# shield-st7735_1_8-spi-UNO-r4.net
KiCad netlist of a schematic drawn in EAGLE
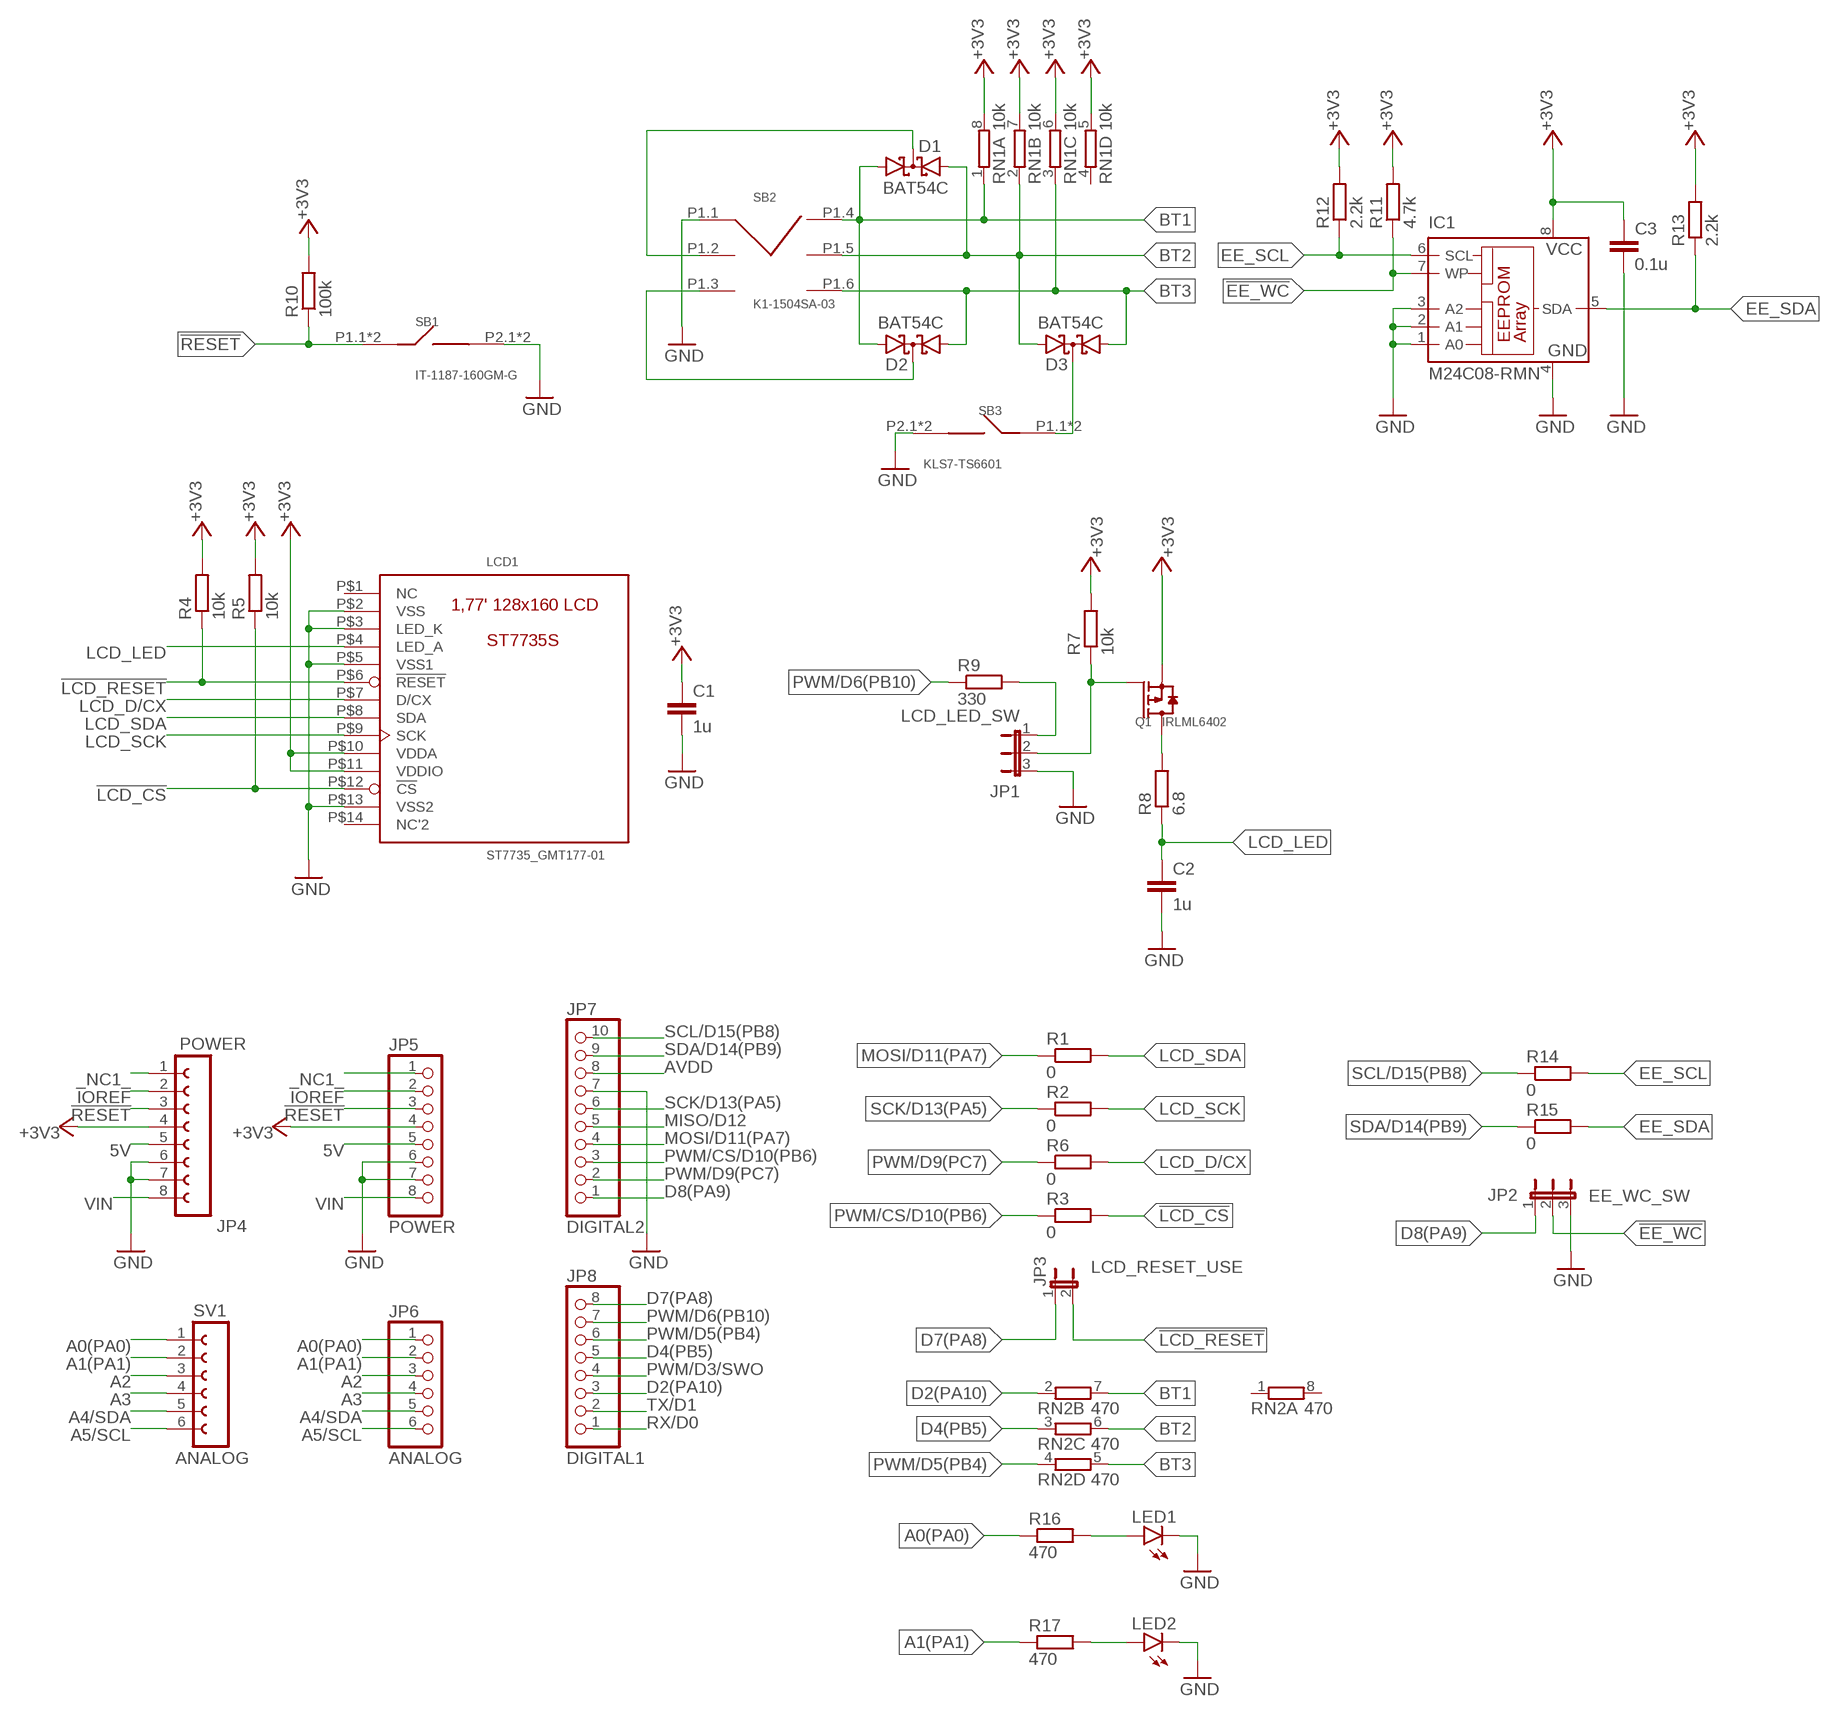
[diagram p0: schematic, sheet 1]

(export (version "E")
  (design (tool "Eeschema 10.0.6"))
  (components
    (comp (ref "C1")
      (value "1u")
      (footprint "eagle-import:C1206")
      (libsource (lib "eagle-import") (part "C-EUC1206"))
    )
    (comp (ref "C2")
      (value "1u")
      (footprint "eagle-import:C1206")
      (libsource (lib "eagle-import") (part "C-EUC1206"))
    )
    (comp (ref "C3")
      (value "0.1u")
      (footprint "eagle-import:C1206")
      (libsource (lib "eagle-import") (part "C-EUC1206"))
    )
    (comp (ref "D1")
      (value "BAT54C")
      (footprint "eagle-import:SOT23")
      (libsource (lib "eagle-import") (part "BAT54C"))
    )
    (comp (ref "D2")
      (value "BAT54C")
      (footprint "eagle-import:SOT23")
      (libsource (lib "eagle-import") (part "BAT54C"))
    )
    (comp (ref "D3")
      (value "BAT54C")
      (footprint "eagle-import:SOT23")
      (libsource (lib "eagle-import") (part "BAT54C"))
    )
    (comp (ref "IC1")
      (value "M24C08-RMN")
      (footprint "eagle-import:SO-08")
      (fields (field (name "MPN") "24LC08B/SN"))
      (libsource (lib "eagle-import") (part "24SNLC08B"))
    )
    (comp (ref "JP1")
      (value "LCD_LED_SW")
      (footprint "eagle-import:JP2")
      (libsource (lib "eagle-import") (part "JP2E"))
    )
    (comp (ref "JP2")
      (value "EE_WC_SW")
      (footprint "eagle-import:JP2")
      (libsource (lib "eagle-import") (part "JP2E"))
    )
    (comp (ref "JP3")
      (value "LCD_RESET_USE")
      (footprint "eagle-import:JP1")
      (libsource (lib "eagle-import") (part "JP1E"))
    )
    (comp (ref "JP4")
      (value "POWER")
      (footprint "eagle-import:FE08")
      (libsource (lib "eagle-import") (part "FE08-1"))
    )
    (comp (ref "JP5")
      (value "POWER")
      (footprint "eagle-import:1X08")
      (libsource (lib "eagle-import") (part "PINHD-1X8"))
    )
    (comp (ref "JP6")
      (value "ANALOG")
      (footprint "eagle-import:1X06")
      (libsource (lib "eagle-import") (part "PINHD-1X6"))
    )
    (comp (ref "JP7")
      (value "DIGITAL2")
      (footprint "eagle-import:1X10")
      (libsource (lib "eagle-import") (part "PINHD-1X10"))
    )
    (comp (ref "JP8")
      (value "DIGITAL1")
      (footprint "eagle-import:1X08")
      (libsource (lib "eagle-import") (part "PINHD-1X8"))
    )
    (comp (ref "LCD1")
      (value "ST7735_GMT177-01")
      (footprint "eagle-import:GMT177-01")
      (libsource (lib "eagle-import") (part "ST7735_GMT177-01"))
    )
    (comp (ref "LED1")
      (value "LEDCHIP-LED0805")
      (footprint "eagle-import:CHIP-LED0805")
      (libsource (lib "eagle-import") (part "LEDCHIP-LED0805"))
    )
    (comp (ref "LED2")
      (value "LEDCHIP-LED0805")
      (footprint "eagle-import:CHIP-LED0805")
      (libsource (lib "eagle-import") (part "LEDCHIP-LED0805"))
    )
    (comp (ref "Q1")
      (value "IRLML6402")
      (footprint "eagle-import:SOT23")
      (libsource (lib "eagle-import") (part "IRLML6402"))
    )
    (comp (ref "R1")
      (value "0")
      (footprint "eagle-import:R1206")
      (libsource (lib "eagle-import") (part "R-EU_R1206"))
    )
    (comp (ref "R2")
      (value "0")
      (footprint "eagle-import:R1206")
      (libsource (lib "eagle-import") (part "R-EU_R1206"))
    )
    (comp (ref "R3")
      (value "0")
      (footprint "eagle-import:R1206")
      (libsource (lib "eagle-import") (part "R-EU_R1206"))
    )
    (comp (ref "R4")
      (value "10k")
      (footprint "eagle-import:R1206")
      (libsource (lib "eagle-import") (part "R-EU_R1206"))
    )
    (comp (ref "R5")
      (value "10k")
      (footprint "eagle-import:R1206")
      (libsource (lib "eagle-import") (part "R-EU_R1206"))
    )
    (comp (ref "R6")
      (value "0")
      (footprint "eagle-import:R1206")
      (libsource (lib "eagle-import") (part "R-EU_R1206"))
    )
    (comp (ref "R7")
      (value "10k")
      (footprint "eagle-import:R1206")
      (libsource (lib "eagle-import") (part "R-EU_R1206"))
    )
    (comp (ref "R8")
      (value "6.8")
      (footprint "eagle-import:R1206")
      (libsource (lib "eagle-import") (part "R-EU_R1206"))
    )
    (comp (ref "R9")
      (value "330")
      (footprint "eagle-import:R1206")
      (libsource (lib "eagle-import") (part "R-EU_R1206"))
    )
    (comp (ref "R10")
      (value "100k")
      (footprint "eagle-import:R1206")
      (libsource (lib "eagle-import") (part "R-EU_R1206"))
    )
    (comp (ref "R11")
      (value "4.7k")
      (footprint "eagle-import:R1206")
      (libsource (lib "eagle-import") (part "R-EU_R1206"))
    )
    (comp (ref "R12")
      (value "2.2k")
      (footprint "eagle-import:R1206")
      (libsource (lib "eagle-import") (part "R-EU_R1206"))
    )
    (comp (ref "R13")
      (value "2.2k")
      (footprint "eagle-import:R1206")
      (libsource (lib "eagle-import") (part "R-EU_R1206"))
    )
    (comp (ref "R14")
      (value "0")
      (footprint "eagle-import:R1206")
      (libsource (lib "eagle-import") (part "R-EU_R1206"))
    )
    (comp (ref "R15")
      (value "0")
      (footprint "eagle-import:R1206")
      (libsource (lib "eagle-import") (part "R-EU_R1206"))
    )
    (comp (ref "R16")
      (value "470")
      (footprint "eagle-import:R1206")
      (libsource (lib "eagle-import") (part "R-EU_R1206"))
    )
    (comp (ref "R17")
      (value "470")
      (footprint "eagle-import:R1206")
      (libsource (lib "eagle-import") (part "R-EU_R1206"))
    )
    (comp (ref "RN1")
      (value "10k")
      (footprint "eagle-import:EXB38V")
      (libsource (lib "eagle-import") (part "4R-NEXB38V"))
    )
    (comp (ref "RN2")
      (value "470")
      (footprint "eagle-import:EXB38V")
      (libsource (lib "eagle-import") (part "4R-NEXB38V"))
    )
    (comp (ref "SB1")
      (value "IT-1187-160GM-G")
      (footprint "eagle-import:IT-1187-160GM-G")
      (libsource (lib "eagle-import") (part "IT-1187-160GM-G"))
    )
    (comp (ref "SB2")
      (value "K1-1504SA-03")
      (footprint "eagle-import:K1-1504SA-3")
      (libsource (lib "eagle-import") (part "K1-1504SA-03"))
    )
    (comp (ref "SB3")
      (value "KLS7-TS6601")
      (footprint "eagle-import:KLS7-TS6601")
      (libsource (lib "eagle-import") (part "KLS7-TS6601"))
    )
    (comp (ref "SV1")
      (value "ANALOG")
      (footprint "eagle-import:FE06")
      (libsource (lib "eagle-import") (part "FE06-1"))
    )
  )
  (nets
    (net (code "1") (name "+3V3") (class "Default")
      (node (ref "C1") (pin "1") (pinfunction "1_1") (pintype "passive"))
      (node (ref "C3") (pin "1") (pinfunction "1_1") (pintype "passive"))
      (node (ref "IC1") (pin "8") (pinfunction "VCC_8") (pintype "power_in"))
      (node (ref "JP4") (pin "4") (pinfunction "4_4") (pintype "passive"))
      (node (ref "JP5") (pin "4") (pinfunction "4_4") (pintype "passive"))
      (node (ref "LCD1") (pin "P$10") (pinfunction "VDDA_P$10") (pintype "power_in"))
      (node (ref "LCD1") (pin "P$11") (pinfunction "VDDIO_P$11") (pintype "power_in"))
      (node (ref "Q1") (pin "2") (pinfunction "S_2") (pintype "passive"))
      (node (ref "R10") (pin "2") (pinfunction "2_2") (pintype "passive"))
      (node (ref "R11") (pin "2") (pinfunction "2_2") (pintype "passive"))
      (node (ref "R12") (pin "2") (pinfunction "2_2") (pintype "passive"))
      (node (ref "R13") (pin "2") (pinfunction "2_2") (pintype "passive"))
      (node (ref "R4") (pin "2") (pinfunction "2_2") (pintype "passive"))
      (node (ref "R5") (pin "2") (pinfunction "2_2") (pintype "passive"))
      (node (ref "R7") (pin "2") (pinfunction "2_2") (pintype "passive"))
      (node (ref "RN1") (pin "5") (pinfunction "2_5") (pintype "passive"))
      (node (ref "RN1") (pin "6") (pinfunction "2_6") (pintype "passive"))
      (node (ref "RN1") (pin "7") (pinfunction "2_7") (pintype "passive"))
      (node (ref "RN1") (pin "8") (pinfunction "2_8") (pintype "passive"))
    )
    (net (code "2") (name "/5V") (class "Default")
      (node (ref "JP4") (pin "5") (pinfunction "5_5") (pintype "passive"))
      (node (ref "JP5") (pin "5") (pinfunction "5_5") (pintype "passive"))
    )
    (net (code "3") (name "/A2") (class "Default")
      (node (ref "JP6") (pin "3") (pinfunction "3_3") (pintype "passive"))
      (node (ref "SV1") (pin "3") (pinfunction "3_3") (pintype "passive"))
    )
    (net (code "4") (name "/A3") (class "Default")
      (node (ref "JP6") (pin "4") (pinfunction "4_4") (pintype "passive"))
      (node (ref "SV1") (pin "4") (pinfunction "4_4") (pintype "passive"))
    )
    (net (code "5") (name "/A4{slash}SDA") (class "Default")
      (node (ref "JP6") (pin "5") (pinfunction "5_5") (pintype "passive"))
      (node (ref "SV1") (pin "5") (pinfunction "5_5") (pintype "passive"))
    )
    (net (code "6") (name "/A5{slash}SCL") (class "Default")
      (node (ref "JP6") (pin "6") (pinfunction "6_6") (pintype "passive"))
      (node (ref "SV1") (pin "6") (pinfunction "6_6") (pintype "passive"))
    )
    (net (code "7") (name "/AVDD") (class "Default")
      (node (ref "JP7") (pin "8") (pinfunction "8_8") (pintype "passive"))
    )
    (net (code "8") (name "/IOREF") (class "Default")
      (node (ref "JP4") (pin "2") (pinfunction "2_2") (pintype "passive"))
      (node (ref "JP5") (pin "2") (pinfunction "2_2") (pintype "passive"))
    )
    (net (code "9") (name "/MISO{slash}D12") (class "Default")
      (node (ref "JP7") (pin "5") (pinfunction "5_5") (pintype "passive"))
    )
    (net (code "10") (name "/PWM{slash}D3{slash}SWO") (class "Default")
      (node (ref "JP8") (pin "4") (pinfunction "4_4") (pintype "passive"))
    )
    (net (code "11") (name "/RX{slash}D0") (class "Default")
      (node (ref "JP8") (pin "1") (pinfunction "1_1") (pintype "passive"))
    )
    (net (code "12") (name "/TX{slash}D1") (class "Default")
      (node (ref "JP8") (pin "2") (pinfunction "2_2") (pintype "passive"))
    )
    (net (code "13") (name "/VIN") (class "Default")
      (node (ref "JP4") (pin "8") (pinfunction "8_8") (pintype "passive"))
      (node (ref "JP5") (pin "8") (pinfunction "8_8") (pintype "passive"))
    )
    (net (code "14") (name "/_NC1_") (class "Default")
      (node (ref "JP4") (pin "1") (pinfunction "1_1") (pintype "passive"))
      (node (ref "JP5") (pin "1") (pinfunction "1_1") (pintype "passive"))
    )
    (net (code "15") (name "/~{EE_WC}") (class "Default")
      (node (ref "IC1") (pin "7") (pinfunction "WP_7") (pintype "input"))
      (node (ref "JP2") (pin "2") (pinfunction "2_2") (pintype "passive"))
      (node (ref "R11") (pin "1") (pinfunction "1_1") (pintype "passive"))
    )
    (net (code "16") (name "/~{LCD_CS}") (class "Default")
      (node (ref "LCD1") (pin "P$12") (pinfunction "~{CS}_P$12") (pintype "input"))
      (node (ref "R3") (pin "2") (pinfunction "2_2") (pintype "passive"))
      (node (ref "R5") (pin "1") (pinfunction "1_1") (pintype "passive"))
    )
    (net (code "17") (name "/~{LCD_RESET}") (class "Default")
      (node (ref "JP3") (pin "2") (pinfunction "2_2") (pintype "passive"))
      (node (ref "LCD1") (pin "P$6") (pinfunction "~{RESET}_P$6") (pintype "input"))
      (node (ref "R4") (pin "1") (pinfunction "1_1") (pintype "passive"))
    )
    (net (code "18") (name "/~{RESET}") (class "Default")
      (node (ref "JP4") (pin "3") (pinfunction "3_3") (pintype "passive"))
      (node (ref "JP5") (pin "3") (pinfunction "3_3") (pintype "passive"))
      (node (ref "R10") (pin "1") (pinfunction "1_1") (pintype "passive"))
      (node (ref "SB1") (pin "P1.1") (pinfunction "P1_P1.1") (pintype "bidirectional"))
      (node (ref "SB1") (pin "P1.2") (pinfunction "P1_P1.2") (pintype "bidirectional"))
    )
    (net (code "19") (name "A0(PA0)") (class "Default")
      (node (ref "JP6") (pin "1") (pinfunction "1_1") (pintype "passive"))
      (node (ref "R16") (pin "1") (pinfunction "1_1") (pintype "passive"))
      (node (ref "SV1") (pin "1") (pinfunction "1_1") (pintype "passive"))
    )
    (net (code "20") (name "A1(PA1)") (class "Default")
      (node (ref "JP6") (pin "2") (pinfunction "2_2") (pintype "passive"))
      (node (ref "R17") (pin "1") (pinfunction "1_1") (pintype "passive"))
      (node (ref "SV1") (pin "2") (pinfunction "2_2") (pintype "passive"))
    )
    (net (code "21") (name "BT1") (class "Default")
      (node (ref "D1") (pin "1") (pinfunction "A1_1") (pintype "passive"))
      (node (ref "D2") (pin "2") (pinfunction "A2_2") (pintype "passive"))
      (node (ref "RN1") (pin "1") (pinfunction "1_1") (pintype "passive"))
      (node (ref "RN2") (pin "7") (pinfunction "2_7") (pintype "passive"))
      (node (ref "SB2") (pin "P1.4") (pinfunction "P4_P1.4") (pintype "bidirectional"))
    )
    (net (code "22") (name "BT2") (class "Default")
      (node (ref "D1") (pin "2") (pinfunction "A2_2") (pintype "passive"))
      (node (ref "D3") (pin "2") (pinfunction "A2_2") (pintype "passive"))
      (node (ref "RN1") (pin "2") (pinfunction "1_2") (pintype "passive"))
      (node (ref "RN2") (pin "6") (pinfunction "2_6") (pintype "passive"))
      (node (ref "SB2") (pin "P1.5") (pinfunction "P5_P1.5") (pintype "bidirectional"))
    )
    (net (code "23") (name "BT3") (class "Default")
      (node (ref "D2") (pin "1") (pinfunction "A1_1") (pintype "passive"))
      (node (ref "D3") (pin "1") (pinfunction "A1_1") (pintype "passive"))
      (node (ref "RN1") (pin "3") (pinfunction "1_3") (pintype "passive"))
      (node (ref "RN2") (pin "5") (pinfunction "2_5") (pintype "passive"))
      (node (ref "SB2") (pin "P1.6") (pinfunction "P6_P1.6") (pintype "bidirectional"))
    )
    (net (code "24") (name "D2(PA10)") (class "Default")
      (node (ref "JP8") (pin "3") (pinfunction "3_3") (pintype "passive"))
      (node (ref "RN2") (pin "2") (pinfunction "1_2") (pintype "passive"))
    )
    (net (code "25") (name "D4(PB5)") (class "Default")
      (node (ref "JP8") (pin "5") (pinfunction "5_5") (pintype "passive"))
      (node (ref "RN2") (pin "3") (pinfunction "1_3") (pintype "passive"))
    )
    (net (code "26") (name "D7(PA8)") (class "Default")
      (node (ref "JP3") (pin "1") (pinfunction "1_1") (pintype "passive"))
      (node (ref "JP8") (pin "8") (pinfunction "8_8") (pintype "passive"))
    )
    (net (code "27") (name "D8(PA9)") (class "Default")
      (node (ref "JP2") (pin "1") (pinfunction "1_1") (pintype "passive"))
      (node (ref "JP7") (pin "1") (pinfunction "1_1") (pintype "passive"))
    )
    (net (code "28") (name "EE_SCL") (class "Default")
      (node (ref "IC1") (pin "6") (pinfunction "SCL_6") (pintype "input"))
      (node (ref "R12") (pin "1") (pinfunction "1_1") (pintype "passive"))
      (node (ref "R14") (pin "2") (pinfunction "2_2") (pintype "passive"))
    )
    (net (code "29") (name "EE_SDA") (class "Default")
      (node (ref "IC1") (pin "5") (pinfunction "SDA_5") (pintype "bidirectional"))
      (node (ref "R13") (pin "1") (pinfunction "1_1") (pintype "passive"))
      (node (ref "R15") (pin "2") (pinfunction "2_2") (pintype "passive"))
    )
    (net (code "30") (name "GND") (class "Default")
      (node (ref "C1") (pin "2") (pinfunction "2_2") (pintype "passive"))
      (node (ref "C2") (pin "2") (pinfunction "2_2") (pintype "passive"))
      (node (ref "C3") (pin "2") (pinfunction "2_2") (pintype "passive"))
      (node (ref "IC1") (pin "1") (pinfunction "A0_1") (pintype "input"))
      (node (ref "IC1") (pin "2") (pinfunction "A1_2") (pintype "input"))
      (node (ref "IC1") (pin "3") (pinfunction "A2_3") (pintype "input"))
      (node (ref "IC1") (pin "4") (pinfunction "GND_4") (pintype "power_in"))
      (node (ref "JP1") (pin "3") (pinfunction "3_3") (pintype "passive"))
      (node (ref "JP2") (pin "3") (pinfunction "3_3") (pintype "passive"))
      (node (ref "JP4") (pin "6") (pinfunction "6_6") (pintype "passive"))
      (node (ref "JP4") (pin "7") (pinfunction "7_7") (pintype "passive"))
      (node (ref "JP5") (pin "6") (pinfunction "6_6") (pintype "passive"))
      (node (ref "JP5") (pin "7") (pinfunction "7_7") (pintype "passive"))
      (node (ref "JP7") (pin "7") (pinfunction "7_7") (pintype "passive"))
      (node (ref "LCD1") (pin "P$13") (pinfunction "VSS2_P$13") (pintype "power_in"))
      (node (ref "LCD1") (pin "P$2") (pinfunction "VSS_P$2") (pintype "power_in"))
      (node (ref "LCD1") (pin "P$3") (pinfunction "LED_K_P$3") (pintype "bidirectional"))
      (node (ref "LCD1") (pin "P$5") (pinfunction "VSS1_P$5") (pintype "power_in"))
      (node (ref "LED1") (pin "C") (pinfunction "C_C") (pintype "passive"))
      (node (ref "LED2") (pin "C") (pinfunction "C_C") (pintype "passive"))
      (node (ref "SB1") (pin "P2.1") (pinfunction "P2_P2.1") (pintype "bidirectional"))
      (node (ref "SB1") (pin "P2.2") (pinfunction "P2_P2.2") (pintype "bidirectional"))
      (node (ref "SB2") (pin "P1.1") (pinfunction "P1_P1.1") (pintype "bidirectional"))
      (node (ref "SB3") (pin "P2.1") (pinfunction "P2_P2.1") (pintype "bidirectional"))
      (node (ref "SB3") (pin "P2.2") (pinfunction "P2_P2.2") (pintype "bidirectional"))
    )
    (net (code "31") (name "LCD_D{slash}CX") (class "Default")
      (node (ref "LCD1") (pin "P$7") (pinfunction "D/CX_P$7") (pintype "input"))
      (node (ref "R6") (pin "2") (pinfunction "2_2") (pintype "passive"))
    )
    (net (code "32") (name "LCD_LED") (class "Default")
      (node (ref "C2") (pin "1") (pinfunction "1_1") (pintype "passive"))
      (node (ref "LCD1") (pin "P$4") (pinfunction "LED_A_P$4") (pintype "input"))
      (node (ref "R8") (pin "1") (pinfunction "1_1") (pintype "passive"))
    )
    (net (code "33") (name "LCD_SCK") (class "Default")
      (node (ref "LCD1") (pin "P$9") (pinfunction "SCK_P$9") (pintype "bidirectional"))
      (node (ref "R2") (pin "2") (pinfunction "2_2") (pintype "passive"))
    )
    (net (code "34") (name "LCD_SDA") (class "Default")
      (node (ref "LCD1") (pin "P$8") (pinfunction "SDA_P$8") (pintype "bidirectional"))
      (node (ref "R1") (pin "2") (pinfunction "2_2") (pintype "passive"))
    )
    (net (code "35") (name "MOSI{slash}D11(PA7)") (class "Default")
      (node (ref "JP7") (pin "4") (pinfunction "4_4") (pintype "passive"))
      (node (ref "R1") (pin "1") (pinfunction "1_1") (pintype "passive"))
    )
    (net (code "36") (name "Net-(D1-CC)") (class "Default")
      (node (ref "D1") (pin "3") (pinfunction "CC_3") (pintype "passive"))
      (node (ref "SB2") (pin "P1.2") (pinfunction "P2_P1.2") (pintype "bidirectional"))
    )
    (net (code "37") (name "Net-(D2-CC)") (class "Default")
      (node (ref "D2") (pin "3") (pinfunction "CC_3") (pintype "passive"))
      (node (ref "SB2") (pin "P1.3") (pinfunction "P3_P1.3") (pintype "bidirectional"))
    )
    (net (code "38") (name "Net-(D3-CC)") (class "Default")
      (node (ref "D3") (pin "3") (pinfunction "CC_3") (pintype "passive"))
      (node (ref "SB3") (pin "P1.1") (pinfunction "P1_P1.1") (pintype "bidirectional"))
      (node (ref "SB3") (pin "P1.2") (pinfunction "P1_P1.2") (pintype "bidirectional"))
    )
    (net (code "39") (name "Net-(JP1-Pad1)") (class "Default")
      (node (ref "JP1") (pin "1") (pinfunction "1_1") (pintype "passive"))
      (node (ref "R9") (pin "2") (pinfunction "2_2") (pintype "passive"))
    )
    (net (code "40") (name "Net-(LED1-PadA)") (class "Default")
      (node (ref "LED1") (pin "A") (pinfunction "A_A") (pintype "passive"))
      (node (ref "R16") (pin "2") (pinfunction "2_2") (pintype "passive"))
    )
    (net (code "41") (name "Net-(LED2-PadA)") (class "Default")
      (node (ref "LED2") (pin "A") (pinfunction "A_A") (pintype "passive"))
      (node (ref "R17") (pin "2") (pinfunction "2_2") (pintype "passive"))
    )
    (net (code "42") (name "Net-(Q1-D)") (class "Default")
      (node (ref "Q1") (pin "3") (pinfunction "D_3") (pintype "passive"))
      (node (ref "R8") (pin "2") (pinfunction "2_2") (pintype "passive"))
    )
    (net (code "43") (name "Net-(Q1-G)") (class "Default")
      (node (ref "JP1") (pin "2") (pinfunction "2_2") (pintype "passive"))
      (node (ref "Q1") (pin "1") (pinfunction "G_1") (pintype "passive"))
      (node (ref "R7") (pin "1") (pinfunction "1_1") (pintype "passive"))
    )
    (net (code "44") (name "PWM{slash}CS{slash}D10(PB6)") (class "Default")
      (node (ref "JP7") (pin "3") (pinfunction "3_3") (pintype "passive"))
      (node (ref "R3") (pin "1") (pinfunction "1_1") (pintype "passive"))
    )
    (net (code "45") (name "PWM{slash}D5(PB4)") (class "Default")
      (node (ref "JP8") (pin "6") (pinfunction "6_6") (pintype "passive"))
      (node (ref "RN2") (pin "4") (pinfunction "1_4") (pintype "passive"))
    )
    (net (code "46") (name "PWM{slash}D6(PB10)") (class "Default")
      (node (ref "JP8") (pin "7") (pinfunction "7_7") (pintype "passive"))
      (node (ref "R9") (pin "1") (pinfunction "1_1") (pintype "passive"))
    )
    (net (code "47") (name "PWM{slash}D9(PC7)") (class "Default")
      (node (ref "JP7") (pin "2") (pinfunction "2_2") (pintype "passive"))
      (node (ref "R6") (pin "1") (pinfunction "1_1") (pintype "passive"))
    )
    (net (code "48") (name "SCK{slash}D13(PA5)") (class "Default")
      (node (ref "JP7") (pin "6") (pinfunction "6_6") (pintype "passive"))
      (node (ref "R2") (pin "1") (pinfunction "1_1") (pintype "passive"))
    )
    (net (code "49") (name "SCL{slash}D15(PB8)") (class "Default")
      (node (ref "JP7") (pin "10") (pinfunction "10_10") (pintype "passive"))
      (node (ref "R14") (pin "1") (pinfunction "1_1") (pintype "passive"))
    )
    (net (code "50") (name "SDA{slash}D14(PB9)") (class "Default")
      (node (ref "JP7") (pin "9") (pinfunction "9_9") (pintype "passive"))
      (node (ref "R15") (pin "1") (pinfunction "1_1") (pintype "passive"))
    )
    (net (code "51") (name "unconnected-(LCD1-NC'2-PadP$14)") (class "Default")
      (node (ref "LCD1") (pin "P$14") (pinfunction "NC'2_P$14") (pintype "no_connect"))
    )
    (net (code "52") (name "unconnected-(LCD1-NC-PadP$1)") (class "Default")
      (node (ref "LCD1") (pin "P$1") (pinfunction "NC_P$1") (pintype "no_connect"))
    )
    (net (code "53") (name "unconnected-(RN1D-1-Pad4)") (class "Default")
      (node (ref "RN1") (pin "4") (pinfunction "1_4") (pintype "passive"))
    )
    (net (code "54") (name "unconnected-(RN2-Pad1)") (class "Default")
      (node (ref "RN2") (pin "1") (pinfunction "1_1") (pintype "passive"))
    )
    (net (code "55") (name "unconnected-(RN2A-2-Pad8)") (class "Default")
      (node (ref "RN2") (pin "8") (pinfunction "2_8") (pintype "passive"))
    )
  )
)
